# Keypadmacro.net
KiCad netlist of a schematic drawn in Altium Designer
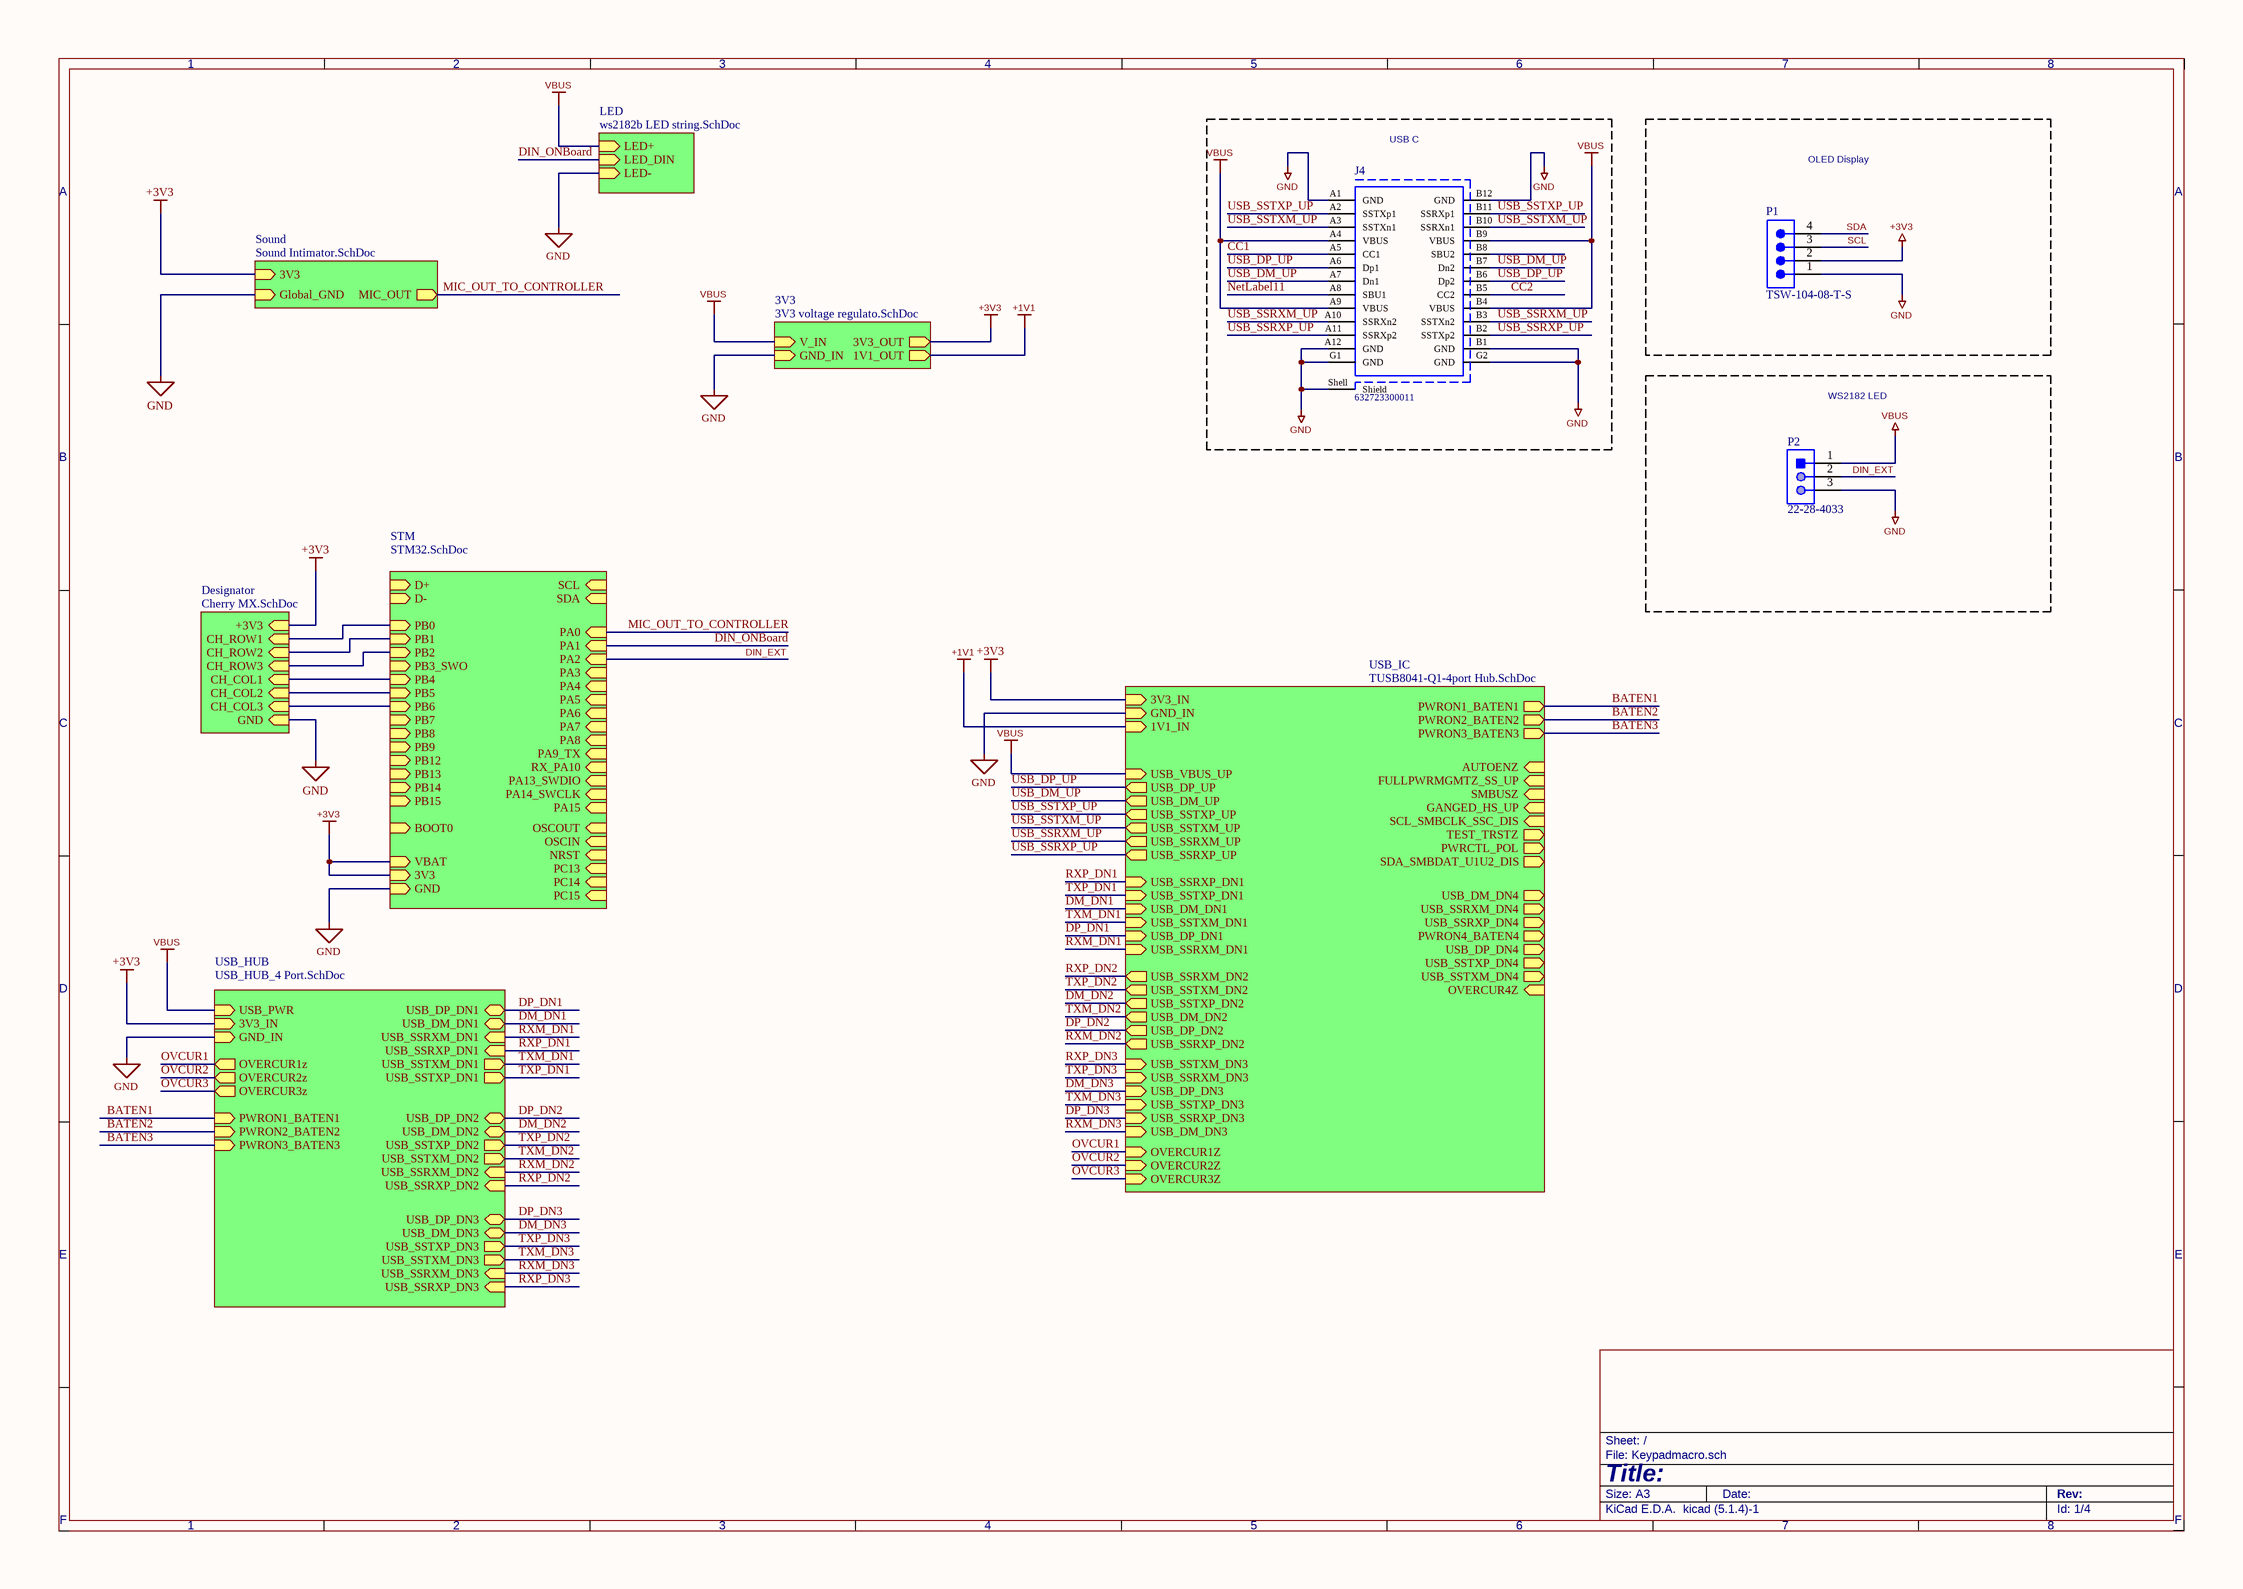
[diagram p0: Keypadmacro.SchDoc]

(export (version "E")
  (design (tool "Eeschema 10.0.6"))
  (components
    (comp (ref "J4")
      (value "632723300011")
      (footprint "632723300011")
      (description "USB 3.1 Type C Receptacle WR-COM, Horizontal, SMT / THT")
      (fields (field (name "MANUFACTURER") "Wurth Elektronik") (field (name "PUBLISHER") "WurthElektronik"))
      (libsource (lib "Altium Content Vault") (part "WE-632723X00011"))
    )
    (comp (ref "P1")
      (value "TSW-104-08-T-S")
      (footprint "SMTC-TSW-104-08-X-S")
      (description "0.025\" SQ Post Header, Through-hole, Vertical, -55 to 105 degC, 2.54 mm Pitch, 4-Pin, Male, RoHS")
      (fields (field (name "MANUFACTURER") "Samtec"))
      (libsource (lib "Altium Content Vault") (part "SMTC-TSW-104-08-X-S"))
    )
    (comp (ref "P2")
      (value "22-28-4033")
      (footprint "MOLX-22-28-4033_V")
      (description "Male Header, Pitch 2.54 mm, 1 x 3 Position, Height 8.38 mm, Tail Length 3.18 mm, RoHS, Bulk")
      (fields (field (name "MANUFACTURER") "Molex"))
      (libsource (lib "Altium Content Vault") (part "CN-1P-M-R3"))
    )
  )
  (nets
    (net (code "2") (name "+3V3") (class "Default")
      (node (ref "P1") (pin "2") (pinfunction "2_2") (pintype "passive"))
    )
    (net (code "8") (name "/CC1") (class "Default")
      (node (ref "J4") (pin "A5") (pinfunction "CC1_A5") (pintype "passive"))
    )
    (net (code "9") (name "/CC2") (class "Default")
      (node (ref "J4") (pin "B5") (pinfunction "CC2_B5") (pintype "passive"))
    )
    (net (code "18") (name "/DIN_EXT") (class "Default")
      (node (ref "P2") (pin "2") (pinfunction "2_2") (pintype "passive"))
    )
    (net (code "30") (name "/NetLabel11") (class "Default")
      (node (ref "J4") (pin "A8") (pinfunction "SBU1_A8") (pintype "passive"))
    )
    (net (code "67") (name "/SCL") (class "Default")
      (node (ref "P1") (pin "3") (pinfunction "3_3") (pintype "passive"))
    )
    (net (code "70") (name "/SDA") (class "Default")
      (node (ref "P1") (pin "4") (pinfunction "4_4") (pintype "passive"))
    )
    (net (code "82") (name "/USB_DM_UP") (class "Default")
      (node (ref "J4") (pin "A7") (pinfunction "Dn1_A7") (pintype "passive"))
      (node (ref "J4") (pin "B7") (pinfunction "Dn2_B7") (pintype "passive"))
    )
    (net (code "84") (name "/USB_DP_UP") (class "Default")
      (node (ref "J4") (pin "A6") (pinfunction "Dp1_A6") (pintype "passive"))
      (node (ref "J4") (pin "B6") (pinfunction "Dp2_B6") (pintype "passive"))
    )
    (net (code "86") (name "/USB_SSRXM_UP") (class "Default")
      (node (ref "J4") (pin "A10") (pinfunction "SSRXn2_A10") (pintype "passive"))
      (node (ref "J4") (pin "B3") (pinfunction "SSTXn2_B3") (pintype "passive"))
    )
    (net (code "88") (name "/USB_SSRXP_UP") (class "Default")
      (node (ref "J4") (pin "A11") (pinfunction "SSRXp2_A11") (pintype "passive"))
      (node (ref "J4") (pin "B2") (pinfunction "SSTXp2_B2") (pintype "passive"))
    )
    (net (code "90") (name "/USB_SSTXM_UP") (class "Default")
      (node (ref "J4") (pin "A3") (pinfunction "SSTXn1_A3") (pintype "passive"))
      (node (ref "J4") (pin "B10") (pinfunction "SSRXn1_B10") (pintype "passive"))
    )
    (net (code "92") (name "/USB_SSTXP_UP") (class "Default")
      (node (ref "J4") (pin "A2") (pinfunction "SSTXp1_A2") (pintype "passive"))
      (node (ref "J4") (pin "B11") (pinfunction "SSRXp1_B11") (pintype "passive"))
    )
    (net (code "93") (name "GND") (class "Default")
      (node (ref "J4") (pin "A1") (pinfunction "GND_A1") (pintype "passive"))
      (node (ref "J4") (pin "A12") (pinfunction "GND_A12") (pintype "passive"))
      (node (ref "J4") (pin "B1") (pinfunction "GND_B1") (pintype "passive"))
      (node (ref "J4") (pin "B12") (pinfunction "GND_B12") (pintype "passive"))
      (node (ref "J4") (pin "G1") (pinfunction "GND_G1") (pintype "passive"))
      (node (ref "J4") (pin "G2") (pinfunction "GND_G2") (pintype "passive"))
      (node (ref "J4") (pin "Shell") (pinfunction "Shield_Shell") (pintype "passive"))
      (node (ref "P1") (pin "1") (pinfunction "1_1") (pintype "passive"))
      (node (ref "P2") (pin "3") (pinfunction "3_3") (pintype "passive"))
    )
    (net (code "94") (name "VBUS") (class "Default")
      (node (ref "J4") (pin "A4") (pinfunction "VBUS_A4") (pintype "passive"))
      (node (ref "J4") (pin "A9") (pinfunction "VBUS_A9") (pintype "passive"))
      (node (ref "J4") (pin "B4") (pinfunction "VBUS_B4") (pintype "passive"))
      (node (ref "J4") (pin "B9") (pinfunction "VBUS_B9") (pintype "passive"))
      (node (ref "P2") (pin "1") (pinfunction "1_1") (pintype "passive"))
    )
    (net (code "95") (name "unconnected-(J4-SBU2-PadB8)") (class "Default")
      (node (ref "J4") (pin "B8") (pinfunction "SBU2_B8") (pintype "passive"))
    )
  )
)
